# Nixie_Wrist_Clock_V1.net
KiCad netlist of a schematic drawn in EAGLE
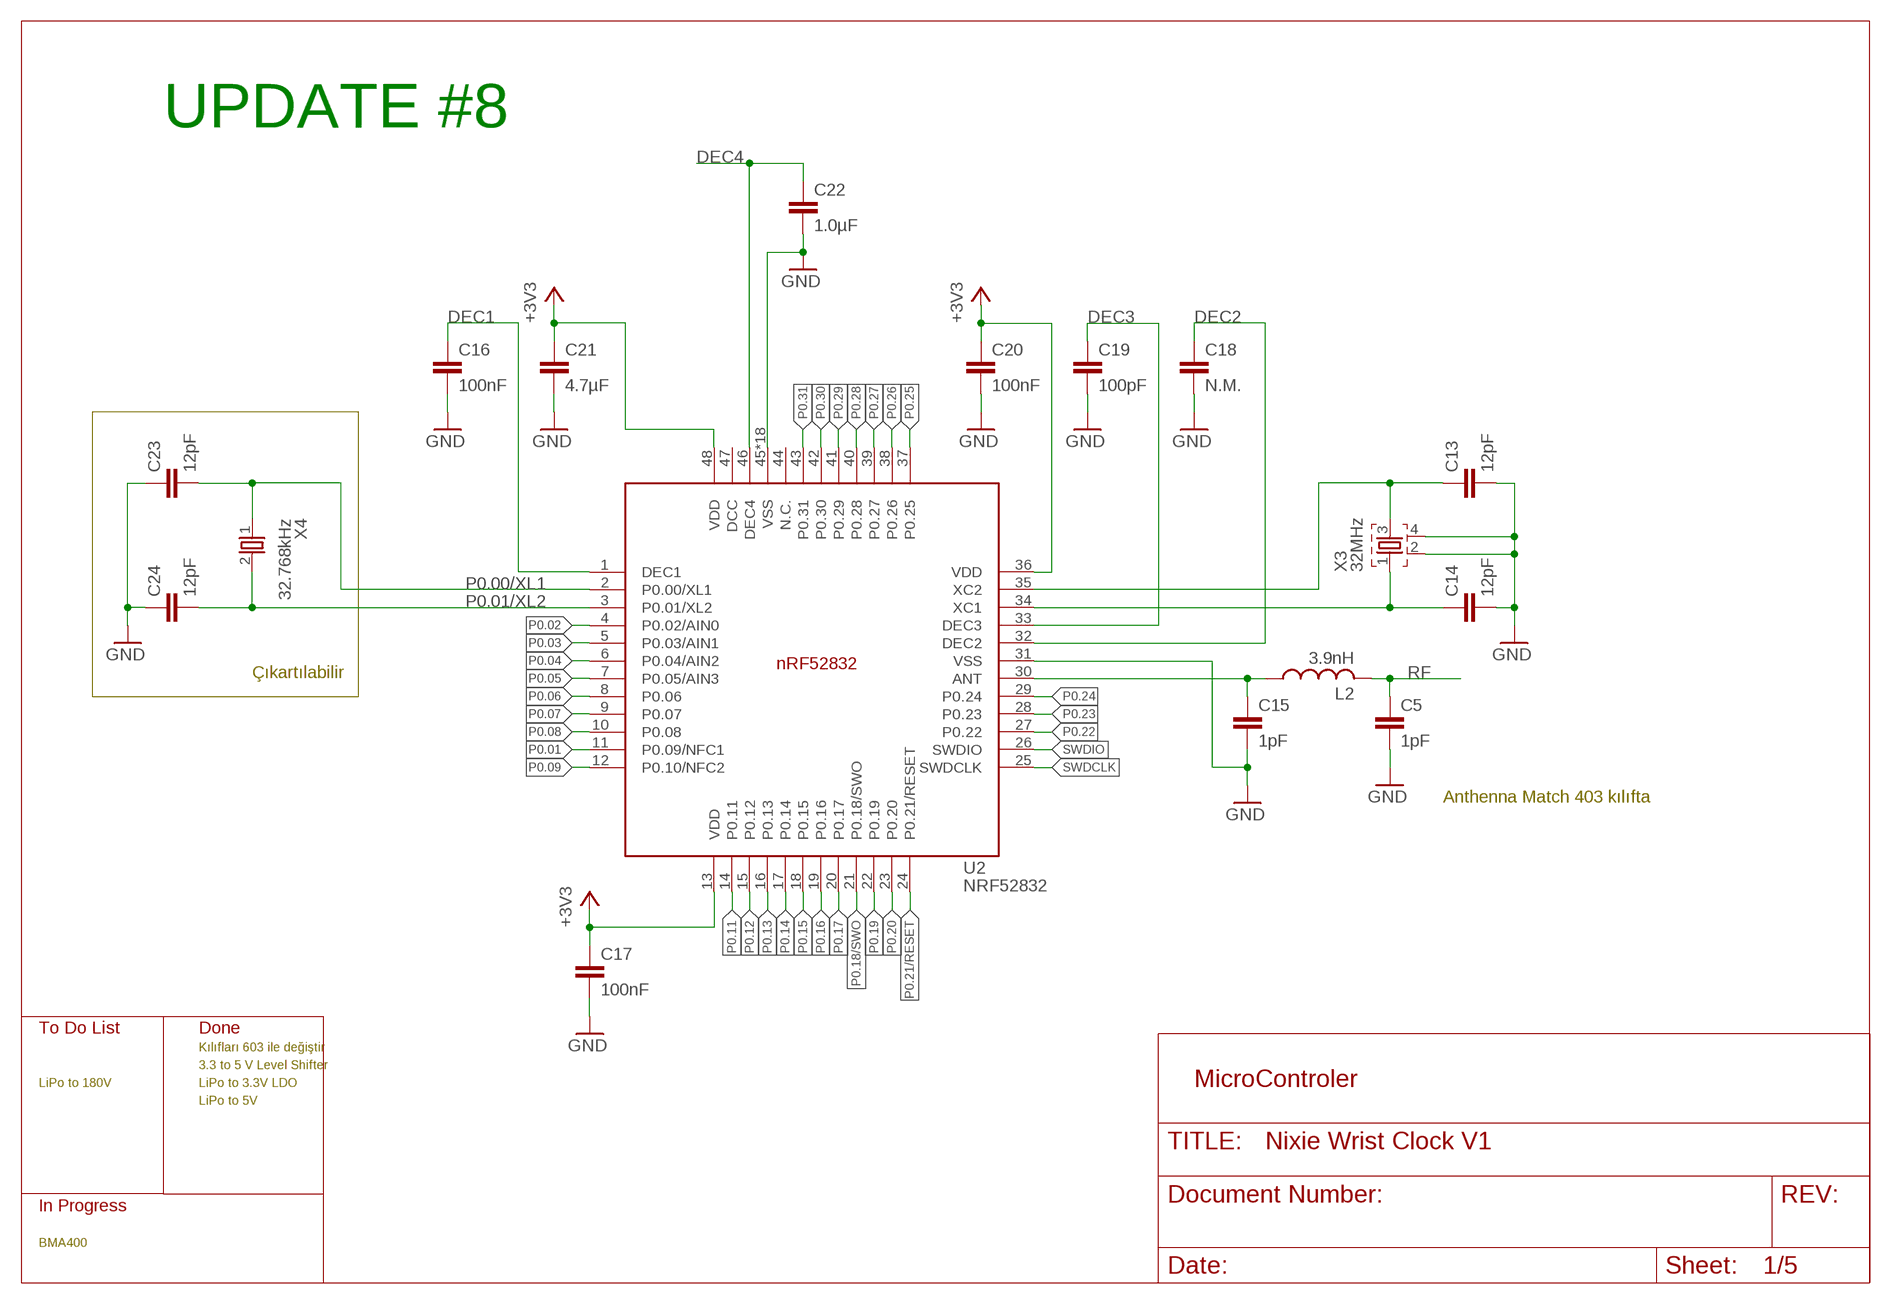
[diagram p0: schematic, sheet 1]
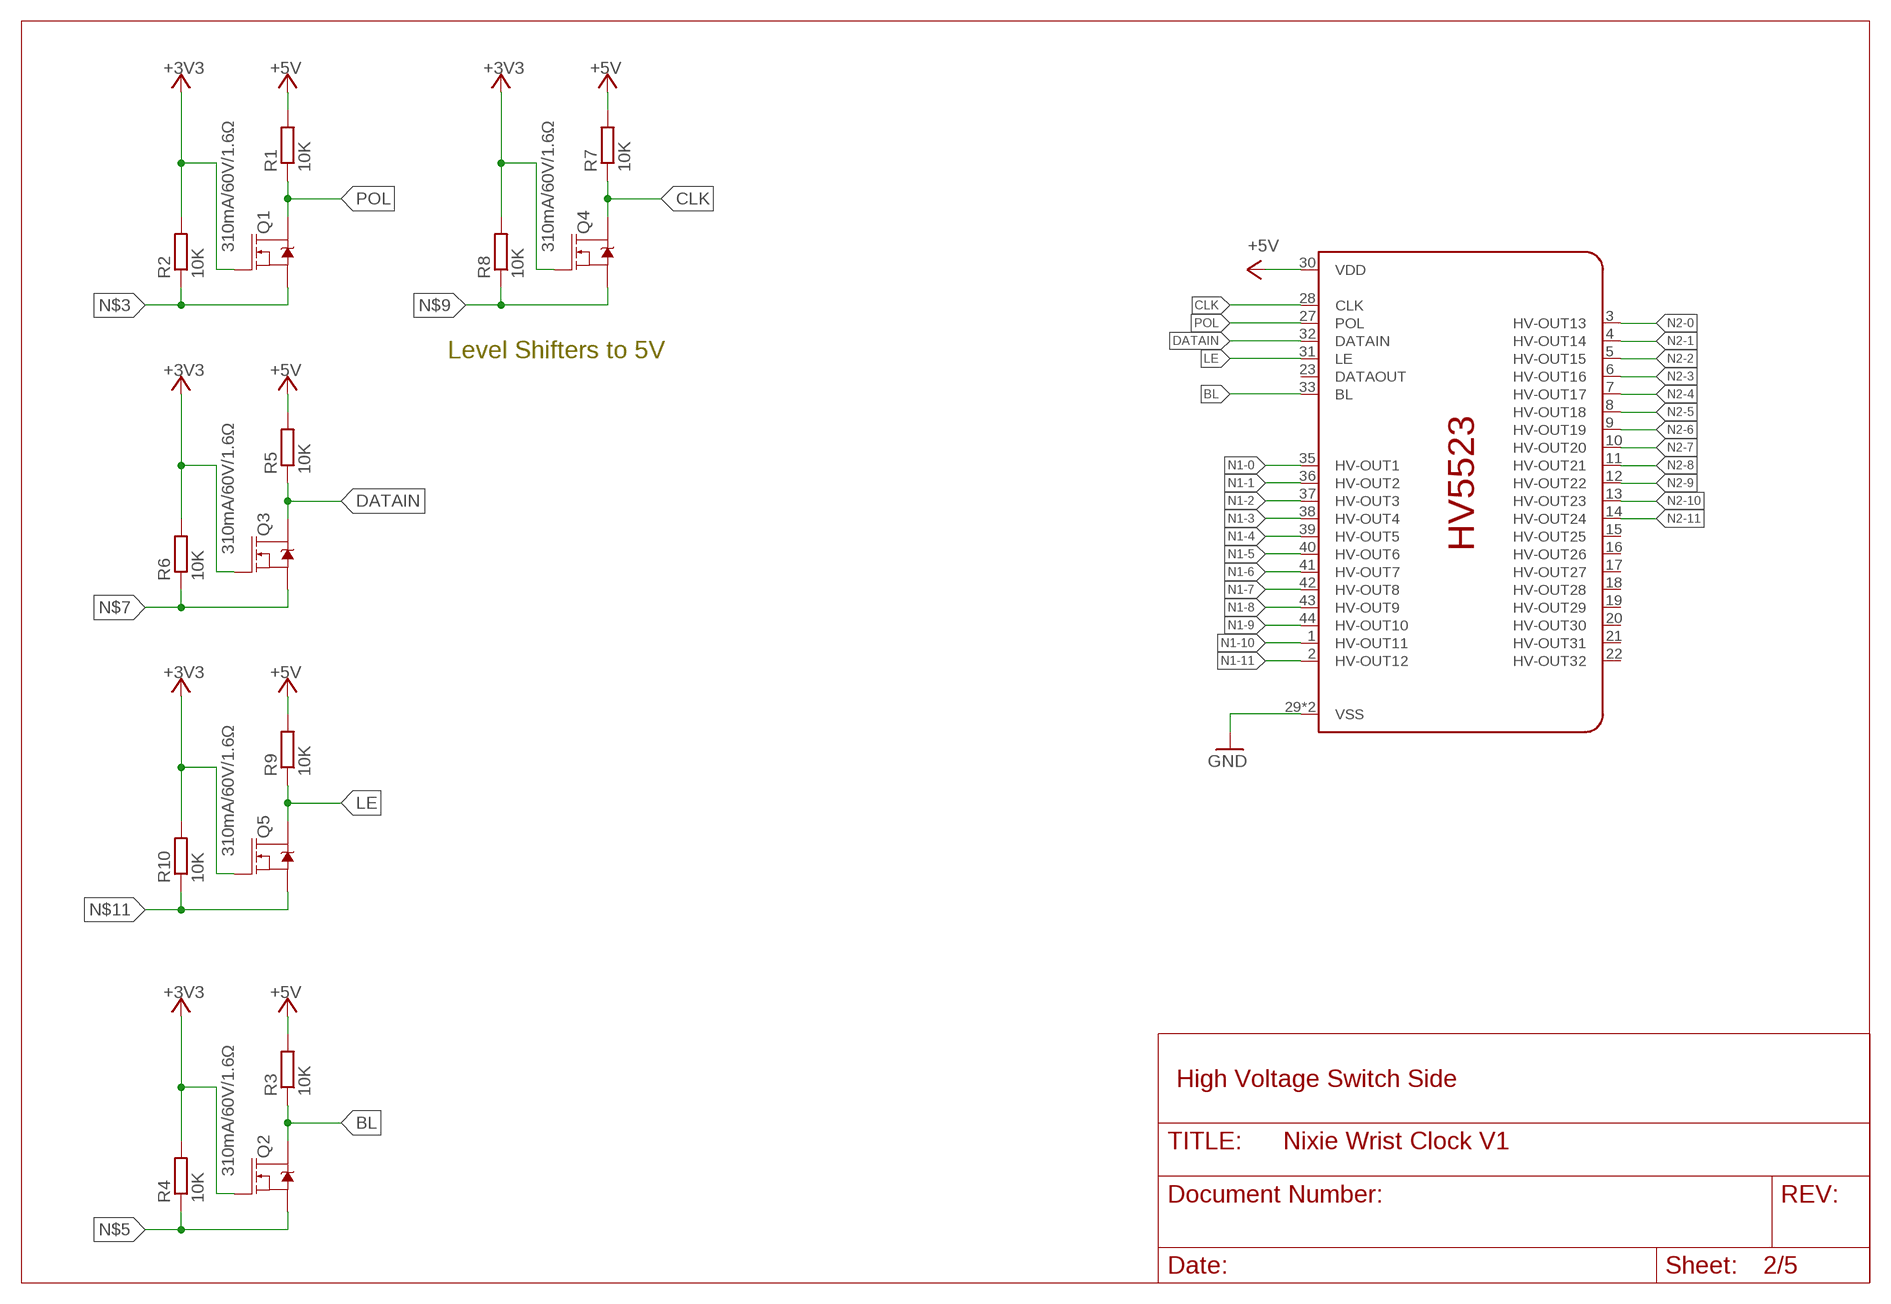
[diagram p1: schematic, sheet 2]
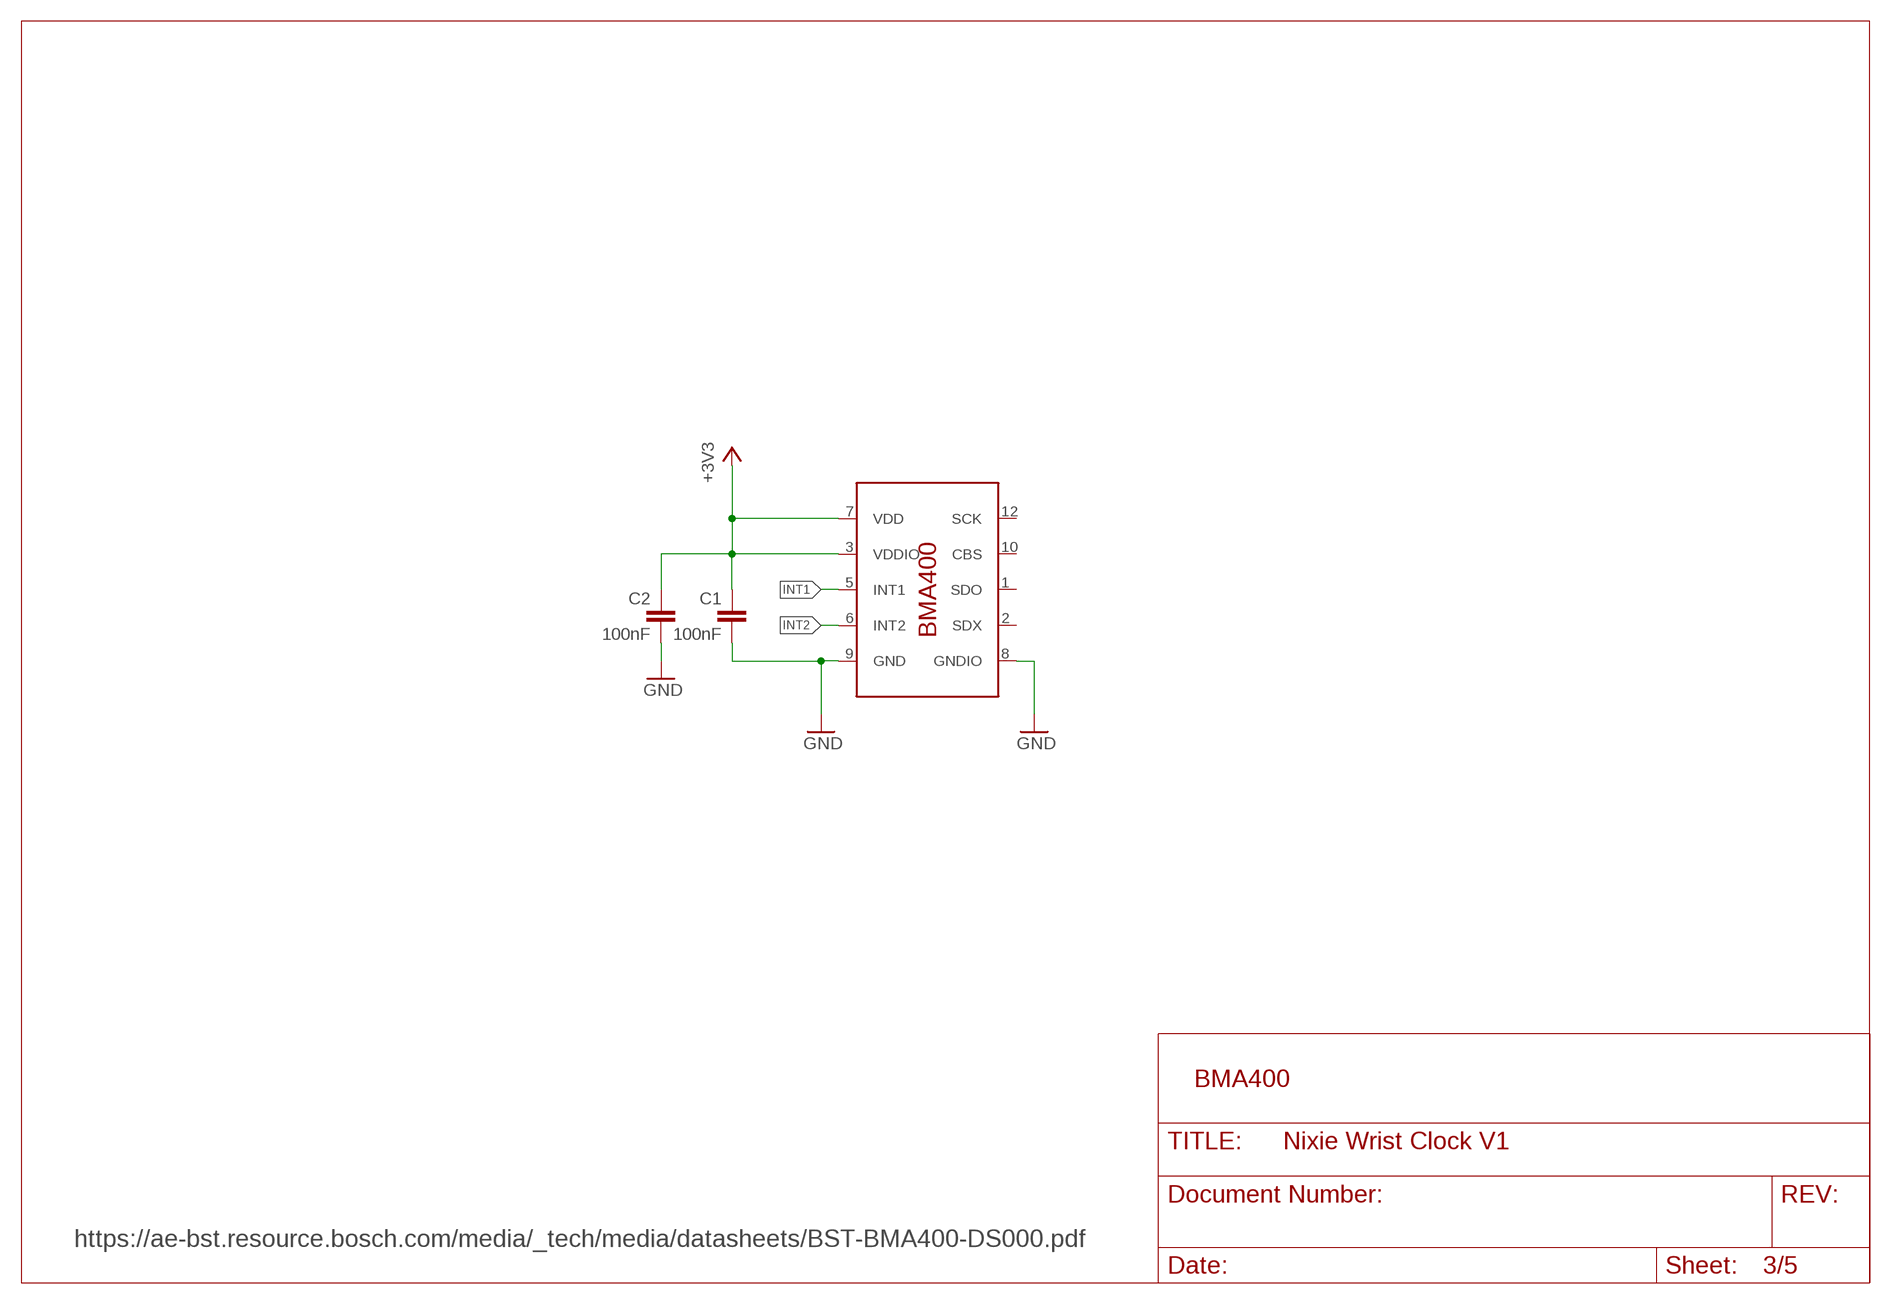
[diagram p2: schematic, sheet 3]
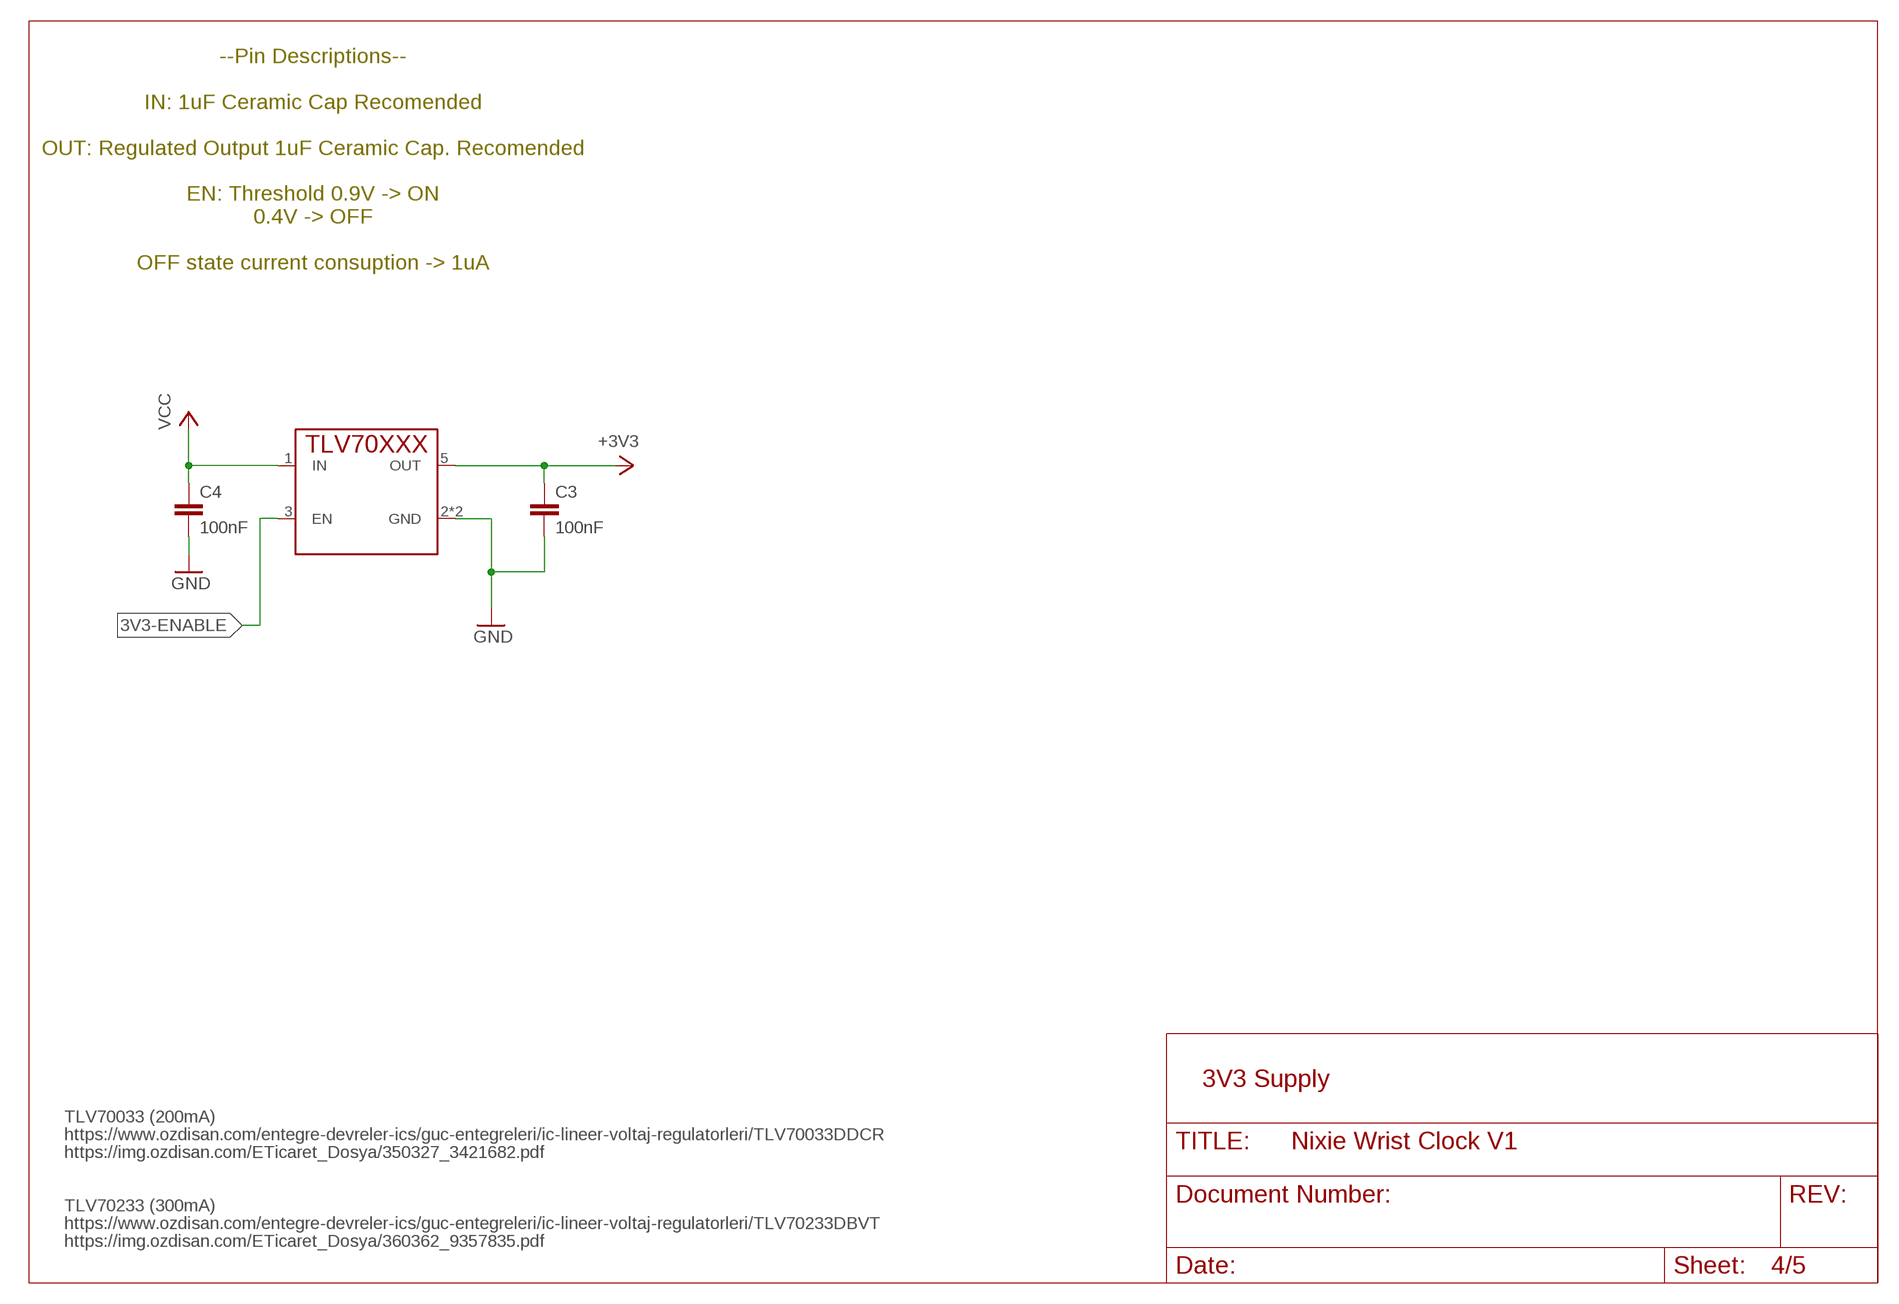
[diagram p3: schematic, sheet 4]
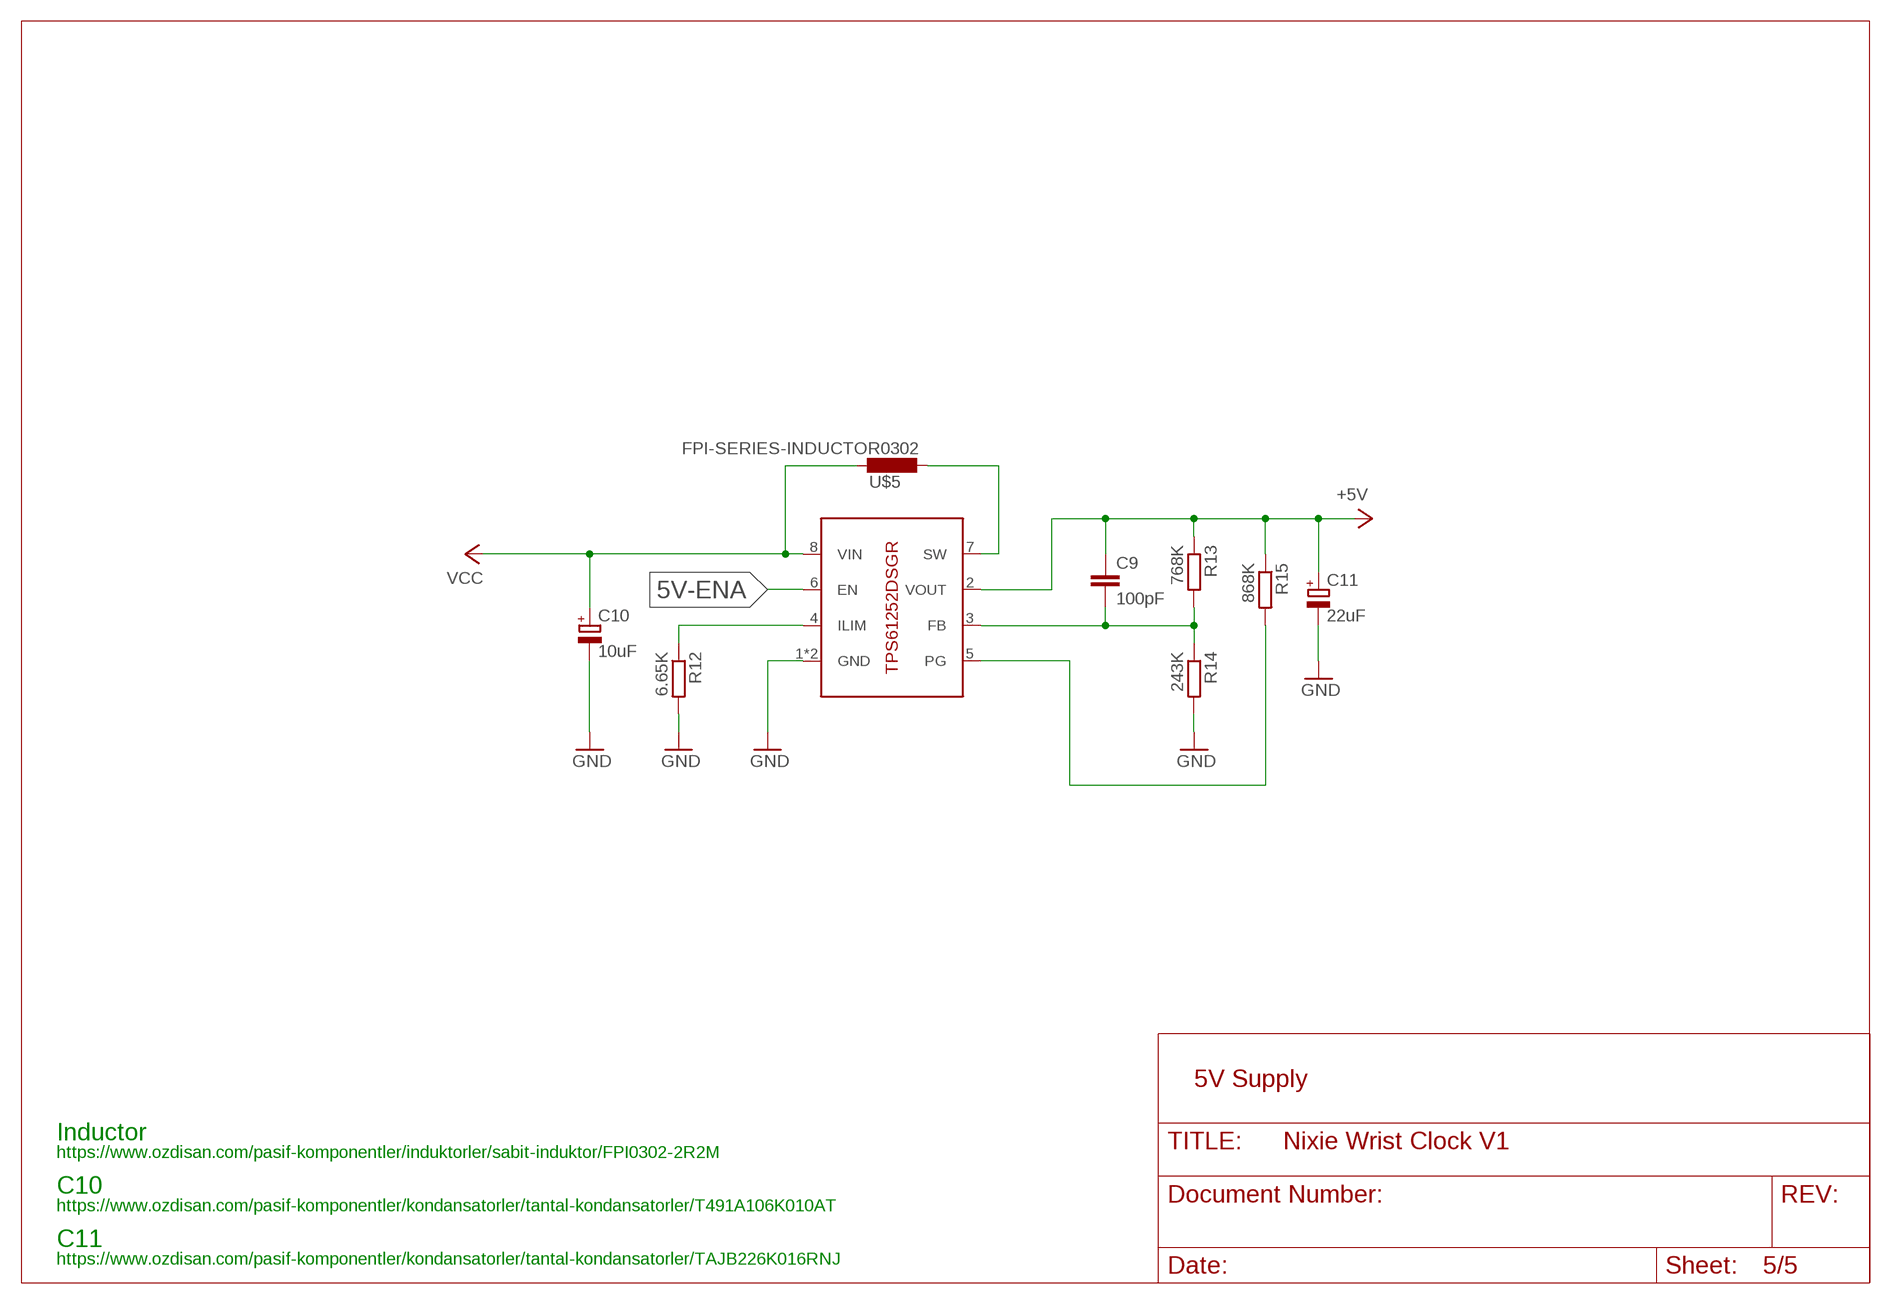
[diagram p4: schematic, sheet 5]

(export (version "E")
  (design (tool "Eeschema 10.0.6"))
  (components
    (comp (ref "C1")
      (value "100nF")
      (footprint "eagle-import:C0603K")
      (libsource (lib "eagle-import") (part "C-EUC0603K"))
    )
    (comp (ref "C2")
      (value "100nF")
      (footprint "eagle-import:C0603K")
      (libsource (lib "eagle-import") (part "C-EUC0603K"))
    )
    (comp (ref "U$1")
      (value "BMA400")
      (footprint "eagle-import:LGA-12")
      (libsource (lib "eagle-import") (part "BMA400"))
    )
    (comp (ref "C3")
      (value "100nF")
      (footprint "eagle-import:RESC0603_N")
      (libsource (lib "eagle-import") (part "CAPACITOR_0603_N"))
    )
    (comp (ref "C4")
      (value "100nF")
      (footprint "eagle-import:RESC0603_N")
      (libsource (lib "eagle-import") (part "CAPACITOR_0603_N"))
    )
    (comp (ref "U$3")
      (value "TLV70233SOT23-5")
      (footprint "eagle-import:SOT23-5")
      (libsource (lib "eagle-import") (part "TLV70233SOT23-5"))
    )
    (comp (ref "C5")
      (value "1pF")
      (footprint "eagle-import:RESC0402_N")
      (libsource (lib "eagle-import") (part "CAPACITOR_0402_N"))
    )
    (comp (ref "C13")
      (value "12pF")
      (footprint "eagle-import:RESC0603_N")
      (libsource (lib "eagle-import") (part "CAPACITOR_0603_N"))
    )
    (comp (ref "C14")
      (value "12pF")
      (footprint "eagle-import:RESC0603_N")
      (libsource (lib "eagle-import") (part "CAPACITOR_0603_N"))
    )
    (comp (ref "C15")
      (value "1pF")
      (footprint "eagle-import:RESC0402_N")
      (libsource (lib "eagle-import") (part "CAPACITOR_0402_N"))
    )
    (comp (ref "C16")
      (value "100nF")
      (footprint "eagle-import:RESC0603_N")
      (libsource (lib "eagle-import") (part "CAPACITOR_0603_N"))
    )
    (comp (ref "C17")
      (value "100nF")
      (footprint "eagle-import:RESC0603_N")
      (libsource (lib "eagle-import") (part "CAPACITOR_0603_N"))
    )
    (comp (ref "C18")
      (value "N.M.")
      (footprint "eagle-import:RESC0603_N")
      (libsource (lib "eagle-import") (part "CAPACITOR_0603_N"))
    )
    (comp (ref "C19")
      (value "100pF")
      (footprint "eagle-import:RESC0603_N")
      (libsource (lib "eagle-import") (part "CAPACITOR_0603_N"))
    )
    (comp (ref "C20")
      (value "100nF")
      (footprint "eagle-import:RESC0603_N")
      (libsource (lib "eagle-import") (part "CAPACITOR_0603_N"))
    )
    (comp (ref "C21")
      (value "4.7µF")
      (footprint "eagle-import:RESC0603_N")
      (libsource (lib "eagle-import") (part "CAPACITOR_0603_N"))
    )
    (comp (ref "C22")
      (value "1.0µF")
      (footprint "eagle-import:RESC0603_N")
      (libsource (lib "eagle-import") (part "CAPACITOR_0603_N"))
    )
    (comp (ref "C23")
      (value "12pF")
      (footprint "eagle-import:RESC0603_N")
      (libsource (lib "eagle-import") (part "CAPACITOR_0603_N"))
    )
    (comp (ref "C24")
      (value "12pF")
      (footprint "eagle-import:RESC0603_N")
      (libsource (lib "eagle-import") (part "CAPACITOR_0603_N"))
    )
    (comp (ref "L2")
      (value "3.9nH")
      (footprint "eagle-import:RESC0402_N")
      (libsource (lib "eagle-import") (part "INDUCTOR_0402_N"))
    )
    (comp (ref "U2")
      (value "NRF52832")
      (footprint "eagle-import:QFN40P600X600X90-48_N")
      (libsource (lib "eagle-import") (part "NRF52832"))
    )
    (comp (ref "X3")
      (value "32MHz")
      (footprint "eagle-import:BT-XTAL_2016_N")
      (libsource (lib "eagle-import") (part "XTAL_32MHZ"))
    )
    (comp (ref "X4")
      (value "32.768kHz")
      (footprint "eagle-import:XTAL_3215_N")
      (libsource (lib "eagle-import") (part "XTAL_32KHZ"))
    )
    (comp (ref "C9")
      (value "100pF")
      (footprint "eagle-import:RESC0603_N")
      (libsource (lib "eagle-import") (part "CAPACITOR_0603_N"))
    )
    (comp (ref "C10")
      (value "10uF")
      (footprint "eagle-import:SMC_A")
      (libsource (lib "eagle-import") (part "CPOL-EUSMCA"))
    )
    (comp (ref "C11")
      (value "22uF")
      (footprint "eagle-import:SMC_B")
      (libsource (lib "eagle-import") (part "CPOL-EUSMCB"))
    )
    (comp (ref "R12")
      (value "6.65K")
      (footprint "eagle-import:R0603")
      (libsource (lib "eagle-import") (part "R-EU_R0603"))
    )
    (comp (ref "R13")
      (value "768K")
      (footprint "eagle-import:R0603")
      (libsource (lib "eagle-import") (part "R-EU_R0603"))
    )
    (comp (ref "R14")
      (value "243K")
      (footprint "eagle-import:R0603")
      (libsource (lib "eagle-import") (part "R-EU_R0603"))
    )
    (comp (ref "R15")
      (value "868K")
      (footprint "eagle-import:R0603")
      (libsource (lib "eagle-import") (part "R-EU_R0603"))
    )
    (comp (ref "U$4")
      (value "TPS61252DSGR")
      (footprint "eagle-import:WSON-8-PAD")
      (libsource (lib "eagle-import") (part "TPS61252DSGR"))
    )
    (comp (ref "U$5")
      (value "FPI-SERIES-INDUCTOR0302")
      (footprint "eagle-import:FPI-0302")
      (libsource (lib "eagle-import") (part "FPI-SERIES-INDUCTOR0302"))
    )
    (comp (ref "Q1")
      (value "310mA/60V/1.6Ω")
      (footprint "eagle-import:SOT323")
      (libsource (lib "eagle-import") (part "MOSFET-NCH-2N7002PW"))
    )
    (comp (ref "Q2")
      (value "310mA/60V/1.6Ω")
      (footprint "eagle-import:SOT323")
      (libsource (lib "eagle-import") (part "MOSFET-NCH-2N7002PW"))
    )
    (comp (ref "Q3")
      (value "310mA/60V/1.6Ω")
      (footprint "eagle-import:SOT323")
      (libsource (lib "eagle-import") (part "MOSFET-NCH-2N7002PW"))
    )
    (comp (ref "Q4")
      (value "310mA/60V/1.6Ω")
      (footprint "eagle-import:SOT323")
      (libsource (lib "eagle-import") (part "MOSFET-NCH-2N7002PW"))
    )
    (comp (ref "Q5")
      (value "310mA/60V/1.6Ω")
      (footprint "eagle-import:SOT323")
      (libsource (lib "eagle-import") (part "MOSFET-NCH-2N7002PW"))
    )
    (comp (ref "R1")
      (value "10K")
      (footprint "eagle-import:R0603")
      (libsource (lib "eagle-import") (part "R-EU_R0603"))
    )
    (comp (ref "R2")
      (value "10K")
      (footprint "eagle-import:R0603")
      (libsource (lib "eagle-import") (part "R-EU_R0603"))
    )
    (comp (ref "R3")
      (value "10K")
      (footprint "eagle-import:R0603")
      (libsource (lib "eagle-import") (part "R-EU_R0603"))
    )
    (comp (ref "R4")
      (value "10K")
      (footprint "eagle-import:R0603")
      (libsource (lib "eagle-import") (part "R-EU_R0603"))
    )
    (comp (ref "R5")
      (value "10K")
      (footprint "eagle-import:R0603")
      (libsource (lib "eagle-import") (part "R-EU_R0603"))
    )
    (comp (ref "R6")
      (value "10K")
      (footprint "eagle-import:R0603")
      (libsource (lib "eagle-import") (part "R-EU_R0603"))
    )
    (comp (ref "R7")
      (value "10K")
      (footprint "eagle-import:R0603")
      (libsource (lib "eagle-import") (part "R-EU_R0603"))
    )
    (comp (ref "R8")
      (value "10K")
      (footprint "eagle-import:R0603")
      (libsource (lib "eagle-import") (part "R-EU_R0603"))
    )
    (comp (ref "R9")
      (value "10K")
      (footprint "eagle-import:R0603")
      (libsource (lib "eagle-import") (part "R-EU_R0603"))
    )
    (comp (ref "R10")
      (value "10K")
      (footprint "eagle-import:R0603")
      (libsource (lib "eagle-import") (part "R-EU_R0603"))
    )
    (comp (ref "U$2")
      (value "HV5523K7")
      (footprint "eagle-import:QFN50P707X707X80-45T515")
      (libsource (lib "eagle-import") (part "HV5523K7"))
    )
  )
  (nets
    (net (code "1") (name "+3V3") (class "Default")
      (node (ref "C1") (pin "2") (pinfunction "2_2") (pintype "passive"))
      (node (ref "C17") (pin "1") (pinfunction "1_1") (pintype "passive"))
      (node (ref "C2") (pin "1") (pinfunction "1_1") (pintype "passive"))
      (node (ref "C20") (pin "1") (pinfunction "1_1") (pintype "passive"))
      (node (ref "C21") (pin "1") (pinfunction "1_1") (pintype "passive"))
      (node (ref "C3") (pin "1") (pinfunction "1_1") (pintype "passive"))
      (node (ref "Q1") (pin "1") (pinfunction "G_1") (pintype "bidirectional"))
      (node (ref "Q2") (pin "1") (pinfunction "G_1") (pintype "bidirectional"))
      (node (ref "Q3") (pin "1") (pinfunction "G_1") (pintype "bidirectional"))
      (node (ref "Q4") (pin "1") (pinfunction "G_1") (pintype "bidirectional"))
      (node (ref "Q5") (pin "1") (pinfunction "G_1") (pintype "bidirectional"))
      (node (ref "R10") (pin "2") (pinfunction "2_2") (pintype "passive"))
      (node (ref "R2") (pin "2") (pinfunction "2_2") (pintype "passive"))
      (node (ref "R4") (pin "2") (pinfunction "2_2") (pintype "passive"))
      (node (ref "R6") (pin "2") (pinfunction "2_2") (pintype "passive"))
      (node (ref "R8") (pin "2") (pinfunction "2_2") (pintype "passive"))
      (node (ref "U$1") (pin "3") (pinfunction "VDDIO_3") (pintype "bidirectional"))
      (node (ref "U$1") (pin "7") (pinfunction "VDD_7") (pintype "bidirectional"))
      (node (ref "U$3") (pin "5") (pinfunction "OUT_5") (pintype "output"))
      (node (ref "U2") (pin "13") (pinfunction "VDD_13") (pintype "power_in"))
      (node (ref "U2") (pin "36") (pinfunction "VDD_36") (pintype "power_in"))
      (node (ref "U2") (pin "48") (pinfunction "VDD_48") (pintype "power_in"))
    )
    (net (code "2") (name "+5V") (class "Default")
      (node (ref "C11") (pin "+") (pinfunction "+_+") (pintype "passive"))
      (node (ref "C9") (pin "1") (pinfunction "1_1") (pintype "passive"))
      (node (ref "R1") (pin "2") (pinfunction "2_2") (pintype "passive"))
      (node (ref "R13") (pin "1") (pinfunction "1_1") (pintype "passive"))
      (node (ref "R15") (pin "1") (pinfunction "1_1") (pintype "passive"))
      (node (ref "R3") (pin "2") (pinfunction "2_2") (pintype "passive"))
      (node (ref "R5") (pin "2") (pinfunction "2_2") (pintype "passive"))
      (node (ref "R7") (pin "2") (pinfunction "2_2") (pintype "passive"))
      (node (ref "R9") (pin "2") (pinfunction "2_2") (pintype "passive"))
      (node (ref "U$2") (pin "30") (pinfunction "VDD_30") (pintype "bidirectional"))
      (node (ref "U$4") (pin "2") (pinfunction "VOUT_2") (pintype "bidirectional"))
    )
    (net (code "3") (name "3V3-ENABLE") (class "Default")
      (node (ref "U$3") (pin "3") (pinfunction "EN_3") (pintype "input"))
    )
    (net (code "4") (name "5V-ENA") (class "Default")
      (node (ref "U$4") (pin "6") (pinfunction "EN_6") (pintype "bidirectional"))
    )
    (net (code "5") (name "BL") (class "Default")
      (node (ref "Q2") (pin "3") (pinfunction "D_3") (pintype "bidirectional"))
      (node (ref "R3") (pin "1") (pinfunction "1_1") (pintype "passive"))
      (node (ref "U$2") (pin "33") (pinfunction "BL_33") (pintype "bidirectional"))
    )
    (net (code "6") (name "CLK") (class "Default")
      (node (ref "Q4") (pin "3") (pinfunction "D_3") (pintype "bidirectional"))
      (node (ref "R7") (pin "1") (pinfunction "1_1") (pintype "passive"))
      (node (ref "U$2") (pin "28") (pinfunction "CLK_28") (pintype "bidirectional"))
    )
    (net (code "7") (name "DATAIN") (class "Default")
      (node (ref "Q3") (pin "3") (pinfunction "D_3") (pintype "bidirectional"))
      (node (ref "R5") (pin "1") (pinfunction "1_1") (pintype "passive"))
      (node (ref "U$2") (pin "32") (pinfunction "DATAIN_32") (pintype "bidirectional"))
    )
    (net (code "8") (name "DEC1") (class "Default")
      (node (ref "C16") (pin "1") (pinfunction "1_1") (pintype "passive"))
      (node (ref "U2") (pin "1") (pinfunction "DEC1_1") (pintype "power_in"))
    )
    (net (code "9") (name "DEC2") (class "Default")
      (node (ref "C18") (pin "1") (pinfunction "1_1") (pintype "passive"))
      (node (ref "U2") (pin "32") (pinfunction "DEC2_32") (pintype "bidirectional"))
    )
    (net (code "10") (name "DEC3") (class "Default")
      (node (ref "C19") (pin "1") (pinfunction "1_1") (pintype "passive"))
      (node (ref "U2") (pin "33") (pinfunction "DEC3_33") (pintype "bidirectional"))
    )
    (net (code "11") (name "DEC4") (class "Default")
      (node (ref "C22") (pin "1") (pinfunction "1_1") (pintype "passive"))
      (node (ref "U2") (pin "46") (pinfunction "DEC4_46") (pintype "power_in"))
    )
    (net (code "12") (name "GND") (class "Default")
      (node (ref "C1") (pin "1") (pinfunction "1_1") (pintype "passive"))
      (node (ref "C10") (pin "-") (pinfunction "-_-") (pintype "passive"))
      (node (ref "C11") (pin "-") (pinfunction "-_-") (pintype "passive"))
      (node (ref "C13") (pin "2") (pinfunction "2_2") (pintype "passive"))
      (node (ref "C14") (pin "2") (pinfunction "2_2") (pintype "passive"))
      (node (ref "C15") (pin "2") (pinfunction "2_2") (pintype "passive"))
      (node (ref "C16") (pin "2") (pinfunction "2_2") (pintype "passive"))
      (node (ref "C17") (pin "2") (pinfunction "2_2") (pintype "passive"))
      (node (ref "C18") (pin "2") (pinfunction "2_2") (pintype "passive"))
      (node (ref "C19") (pin "2") (pinfunction "2_2") (pintype "passive"))
      (node (ref "C2") (pin "2") (pinfunction "2_2") (pintype "passive"))
      (node (ref "C20") (pin "2") (pinfunction "2_2") (pintype "passive"))
      (node (ref "C21") (pin "2") (pinfunction "2_2") (pintype "passive"))
      (node (ref "C22") (pin "2") (pinfunction "2_2") (pintype "passive"))
      (node (ref "C23") (pin "1") (pinfunction "1_1") (pintype "passive"))
      (node (ref "C24") (pin "1") (pinfunction "1_1") (pintype "passive"))
      (node (ref "C3") (pin "2") (pinfunction "2_2") (pintype "passive"))
      (node (ref "C4") (pin "2") (pinfunction "2_2") (pintype "passive"))
      (node (ref "C5") (pin "2") (pinfunction "2_2") (pintype "passive"))
      (node (ref "R12") (pin "2") (pinfunction "2_2") (pintype "passive"))
      (node (ref "R14") (pin "2") (pinfunction "2_2") (pintype "passive"))
      (node (ref "U$1") (pin "8") (pinfunction "GNDIO_8") (pintype "bidirectional"))
      (node (ref "U$1") (pin "9") (pinfunction "GND_9") (pintype "bidirectional"))
      (node (ref "U$2") (pin "29") (pinfunction "VSS_29") (pintype "bidirectional"))
      (node (ref "U$2") (pin "45") (pinfunction "VSS_45") (pintype "bidirectional"))
      (node (ref "U$3") (pin "2") (pinfunction "GND_2") (pintype "bidirectional"))
      (node (ref "U$3") (pin "4") (pinfunction "GND_4") (pintype "bidirectional"))
      (node (ref "U$4") (pin "1") (pinfunction "GND_1") (pintype "bidirectional"))
      (node (ref "U$4") (pin "PAD") (pinfunction "GND_PAD") (pintype "bidirectional"))
      (node (ref "U2") (pin "31") (pinfunction "VSS_31") (pintype "bidirectional"))
      (node (ref "U2") (pin "45") (pinfunction "VSS_45") (pintype "power_in"))
      (node (ref "U2") (pin "PAD") (pinfunction "VSS_PAD") (pintype "power_in"))
      (node (ref "U2") (pin "PAD@VIA01") (pinfunction "VSS_PAD@VIA01") (pintype "power_in"))
      (node (ref "U2") (pin "PAD@VIA02") (pinfunction "VSS_PAD@VIA02") (pintype "power_in"))
      (node (ref "U2") (pin "PAD@VIA03") (pinfunction "VSS_PAD@VIA03") (pintype "power_in"))
      (node (ref "U2") (pin "PAD@VIA04") (pinfunction "VSS_PAD@VIA04") (pintype "power_in"))
      (node (ref "U2") (pin "PAD@VIA05") (pinfunction "VSS_PAD@VIA05") (pintype "power_in"))
      (node (ref "U2") (pin "PAD@VIA06") (pinfunction "VSS_PAD@VIA06") (pintype "power_in"))
      (node (ref "U2") (pin "PAD@VIA07") (pinfunction "VSS_PAD@VIA07") (pintype "power_in"))
      (node (ref "U2") (pin "PAD@VIA08") (pinfunction "VSS_PAD@VIA08") (pintype "power_in"))
      (node (ref "U2") (pin "PAD@VIA09") (pinfunction "VSS_PAD@VIA09") (pintype "power_in"))
      (node (ref "U2") (pin "PAD@VIA10") (pinfunction "VSS_PAD@VIA10") (pintype "power_in"))
      (node (ref "U2") (pin "PAD@VIA11") (pinfunction "VSS_PAD@VIA11") (pintype "power_in"))
      (node (ref "U2") (pin "PAD@VIA12") (pinfunction "VSS_PAD@VIA12") (pintype "power_in"))
      (node (ref "U2") (pin "PAD@VIA13") (pinfunction "VSS_PAD@VIA13") (pintype "power_in"))
      (node (ref "U2") (pin "PAD@VIA14") (pinfunction "VSS_PAD@VIA14") (pintype "power_in"))
      (node (ref "U2") (pin "PAD@VIA15") (pinfunction "VSS_PAD@VIA15") (pintype "power_in"))
      (node (ref "U2") (pin "PAD@VIA16") (pinfunction "VSS_PAD@VIA16") (pintype "power_in"))
      (node (ref "X3") (pin "2") (pinfunction "2_2") (pintype "passive"))
      (node (ref "X3") (pin "4") (pinfunction "4_4") (pintype "passive"))
    )
    (net (code "13") (name "INT1") (class "Default")
      (node (ref "U$1") (pin "5") (pinfunction "INT1_5") (pintype "bidirectional"))
    )
    (net (code "14") (name "INT2") (class "Default")
      (node (ref "U$1") (pin "6") (pinfunction "INT2_6") (pintype "bidirectional"))
    )
    (net (code "15") (name "LE") (class "Default")
      (node (ref "Q5") (pin "3") (pinfunction "D_3") (pintype "bidirectional"))
      (node (ref "R9") (pin "1") (pinfunction "1_1") (pintype "passive"))
      (node (ref "U$2") (pin "31") (pinfunction "LE_31") (pintype "bidirectional"))
    )
    (net (code "16") (name "N$3") (class "Default")
      (node (ref "Q1") (pin "2") (pinfunction "S_2") (pintype "bidirectional"))
      (node (ref "R2") (pin "1") (pinfunction "1_1") (pintype "passive"))
    )
    (net (code "17") (name "N$5") (class "Default")
      (node (ref "Q2") (pin "2") (pinfunction "S_2") (pintype "bidirectional"))
      (node (ref "R4") (pin "1") (pinfunction "1_1") (pintype "passive"))
    )
    (net (code "18") (name "N$7") (class "Default")
      (node (ref "Q3") (pin "2") (pinfunction "S_2") (pintype "bidirectional"))
      (node (ref "R6") (pin "1") (pinfunction "1_1") (pintype "passive"))
    )
    (net (code "19") (name "N$9") (class "Default")
      (node (ref "Q4") (pin "2") (pinfunction "S_2") (pintype "bidirectional"))
      (node (ref "R8") (pin "1") (pinfunction "1_1") (pintype "passive"))
    )
    (net (code "20") (name "N$11") (class "Default")
      (node (ref "Q5") (pin "2") (pinfunction "S_2") (pintype "bidirectional"))
      (node (ref "R10") (pin "1") (pinfunction "1_1") (pintype "passive"))
    )
    (net (code "21") (name "N1-0") (class "Default")
      (node (ref "U$2") (pin "35") (pinfunction "HV-OUT1_35") (pintype "bidirectional"))
    )
    (net (code "22") (name "N1-1") (class "Default")
      (node (ref "U$2") (pin "36") (pinfunction "HV-OUT2_36") (pintype "bidirectional"))
    )
    (net (code "23") (name "N1-2") (class "Default")
      (node (ref "U$2") (pin "37") (pinfunction "HV-OUT3_37") (pintype "bidirectional"))
    )
    (net (code "24") (name "N1-3") (class "Default")
      (node (ref "U$2") (pin "38") (pinfunction "HV-OUT4_38") (pintype "bidirectional"))
    )
    (net (code "25") (name "N1-4") (class "Default")
      (node (ref "U$2") (pin "39") (pinfunction "HV-OUT5_39") (pintype "bidirectional"))
    )
    (net (code "26") (name "N1-5") (class "Default")
      (node (ref "U$2") (pin "40") (pinfunction "HV-OUT6_40") (pintype "bidirectional"))
    )
    (net (code "27") (name "N1-6") (class "Default")
      (node (ref "U$2") (pin "41") (pinfunction "HV-OUT7_41") (pintype "bidirectional"))
    )
    (net (code "28") (name "N1-7") (class "Default")
      (node (ref "U$2") (pin "42") (pinfunction "HV-OUT8_42") (pintype "bidirectional"))
    )
    (net (code "29") (name "N1-8") (class "Default")
      (node (ref "U$2") (pin "43") (pinfunction "HV-OUT9_43") (pintype "bidirectional"))
    )
    (net (code "30") (name "N1-9") (class "Default")
      (node (ref "U$2") (pin "44") (pinfunction "HV-OUT10_44") (pintype "bidirectional"))
    )
    (net (code "31") (name "N1-10") (class "Default")
      (node (ref "U$2") (pin "1") (pinfunction "HV-OUT11_1") (pintype "bidirectional"))
    )
    (net (code "32") (name "N1-11") (class "Default")
      (node (ref "U$2") (pin "2") (pinfunction "HV-OUT12_2") (pintype "bidirectional"))
    )
    (net (code "33") (name "N2-0") (class "Default")
      (node (ref "U$2") (pin "3") (pinfunction "HV-OUT13_3") (pintype "bidirectional"))
    )
    (net (code "34") (name "N2-1") (class "Default")
      (node (ref "U$2") (pin "4") (pinfunction "HV-OUT14_4") (pintype "bidirectional"))
    )
    (net (code "35") (name "N2-2") (class "Default")
      (node (ref "U$2") (pin "5") (pinfunction "HV-OUT15_5") (pintype "bidirectional"))
    )
    (net (code "36") (name "N2-3") (class "Default")
      (node (ref "U$2") (pin "6") (pinfunction "HV-OUT16_6") (pintype "bidirectional"))
    )
    (net (code "37") (name "N2-4") (class "Default")
      (node (ref "U$2") (pin "7") (pinfunction "HV-OUT17_7") (pintype "bidirectional"))
    )
    (net (code "38") (name "N2-5") (class "Default")
      (node (ref "U$2") (pin "8") (pinfunction "HV-OUT18_8") (pintype "bidirectional"))
    )
    (net (code "39") (name "N2-6") (class "Default")
      (node (ref "U$2") (pin "9") (pinfunction "HV-OUT19_9") (pintype "bidirectional"))
    )
    (net (code "40") (name "N2-7") (class "Default")
      (node (ref "U$2") (pin "10") (pinfunction "HV-OUT20_10") (pintype "bidirectional"))
    )
    (net (code "41") (name "N2-8") (class "Default")
      (node (ref "U$2") (pin "11") (pinfunction "HV-OUT21_11") (pintype "bidirectional"))
    )
    (net (code "42") (name "N2-9") (class "Default")
      (node (ref "U$2") (pin "12") (pinfunction "HV-OUT22_12") (pintype "bidirectional"))
    )
    (net (code "43") (name "N2-10") (class "Default")
      (node (ref "U$2") (pin "13") (pinfunction "HV-OUT23_13") (pintype "bidirectional"))
    )
    (net (code "44") (name "N2-11") (class "Default")
      (node (ref "U$2") (pin "14") (pinfunction "HV-OUT24_14") (pintype "bidirectional"))
    )
    (net (code "45") (name "Net-(U$4-FB)") (class "Default")
      (node (ref "C9") (pin "2") (pinfunction "2_2") (pintype "passive"))
      (node (ref "R13") (pin "2") (pinfunction "2_2") (pintype "passive"))
      (node (ref "R14") (pin "1") (pinfunction "1_1") (pintype "passive"))
      (node (ref "U$4") (pin "3") (pinfunction "FB_3") (pintype "bidirectional"))
    )
    (net (code "46") (name "Net-(U$4-ILIM)") (class "Default")
      (node (ref "R12") (pin "1") (pinfunction "1_1") (pintype "passive"))
      (node (ref "U$4") (pin "4") (pinfunction "ILIM_4") (pintype "bidirectional"))
    )
    (net (code "47") (name "Net-(U$4-PG)") (class "Default")
      (node (ref "R15") (pin "2") (pinfunction "2_2") (pintype "passive"))
      (node (ref "U$4") (pin "5") (pinfunction "PG_5") (pintype "bidirectional"))
    )
    (net (code "48") (name "Net-(U$4-SW)") (class "Default")
      (node (ref "U$4") (pin "7") (pinfunction "SW_7") (pintype "bidirectional"))
      (node (ref "U$5") (pin "P$2") (pinfunction "2_P$2") (pintype "passive"))
    )
    (net (code "49") (name "Net-(U2-ANT)") (class "Default")
      (node (ref "C15") (pin "1") (pinfunction "1_1") (pintype "passive"))
      (node (ref "L2") (pin "1") (pinfunction "1_1") (pintype "passive"))
      (node (ref "U2") (pin "30") (pinfunction "ANT_30") (pintype "bidirectional"))
    )
    (net (code "50") (name "Net-(U2-XC1)") (class "Default")
      (node (ref "C14") (pin "1") (pinfunction "1_1") (pintype "passive"))
      (node (ref "U2") (pin "34") (pinfunction "XC1_34") (pintype "input"))
      (node (ref "X3") (pin "1") (pinfunction "1_1") (pintype "passive"))
    )
    (net (code "51") (name "Net-(U2-XC2)") (class "Default")
      (node (ref "C13") (pin "1") (pinfunction "1_1") (pintype "passive"))
      (node (ref "U2") (pin "35") (pinfunction "XC2_35") (pintype "output"))
      (node (ref "X3") (pin "3") (pinfunction "3_3") (pintype "passive"))
    )
    (net (code "52") (name "P0.00{slash}XL1") (class "Default")
      (node (ref "C23") (pin "2") (pinfunction "2_2") (pintype "passive"))
      (node (ref "U2") (pin "2") (pinfunction "P0.00/XL1_2") (pintype "bidirectional"))
      (node (ref "X4") (pin "1") (pinfunction "1_1") (pintype "passive"))
    )
    (net (code "53") (name "P0.01") (class "Default")
      (node (ref "U2") (pin "11") (pinfunction "P0.09/NFC1_11") (pintype "bidirectional"))
    )
    (net (code "54") (name "P0.01{slash}XL2") (class "Default")
      (node (ref "C24") (pin "2") (pinfunction "2_2") (pintype "passive"))
      (node (ref "U2") (pin "3") (pinfunction "P0.01/XL2_3") (pintype "bidirectional"))
      (node (ref "X4") (pin "2") (pinfunction "2_2") (pintype "passive"))
    )
    (net (code "55") (name "P0.02") (class "Default")
      (node (ref "U2") (pin "4") (pinfunction "P0.02/AIN0_4") (pintype "bidirectional"))
    )
    (net (code "56") (name "P0.03") (class "Default")
      (node (ref "U2") (pin "5") (pinfunction "P0.03/AIN1_5") (pintype "bidirectional"))
    )
    (net (code "57") (name "P0.04") (class "Default")
      (node (ref "U2") (pin "6") (pinfunction "P0.04/AIN2_6") (pintype "bidirectional"))
    )
    (net (code "58") (name "P0.05") (class "Default")
      (node (ref "U2") (pin "7") (pinfunction "P0.05/AIN3_7") (pintype "bidirectional"))
    )
    (net (code "59") (name "P0.06") (class "Default")
      (node (ref "U2") (pin "8") (pinfunction "P0.06_8") (pintype "bidirectional"))
    )
    (net (code "60") (name "P0.07") (class "Default")
      (node (ref "U2") (pin "9") (pinfunction "P0.07_9") (pintype "bidirectional"))
    )
    (net (code "61") (name "P0.08") (class "Default")
      (node (ref "U2") (pin "10") (pinfunction "P0.08_10") (pintype "bidirectional"))
    )
    (net (code "62") (name "P0.09") (class "Default")
      (node (ref "U2") (pin "12") (pinfunction "P0.10/NFC2_12") (pintype "bidirectional"))
    )
    (net (code "63") (name "P0.11") (class "Default")
      (node (ref "U2") (pin "14") (pinfunction "P0.11_14") (pintype "bidirectional"))
    )
    (net (code "64") (name "P0.12") (class "Default")
      (node (ref "U2") (pin "15") (pinfunction "P0.12_15") (pintype "bidirectional"))
    )
    (net (code "65") (name "P0.13") (class "Default")
      (node (ref "U2") (pin "16") (pinfunction "P0.13_16") (pintype "bidirectional"))
    )
    (net (code "66") (name "P0.14") (class "Default")
      (node (ref "U2") (pin "17") (pinfunction "P0.14_17") (pintype "bidirectional"))
    )
    (net (code "67") (name "P0.15") (class "Default")
      (node (ref "U2") (pin "18") (pinfunction "P0.15_18") (pintype "bidirectional"))
    )
    (net (code "68") (name "P0.16") (class "Default")
      (node (ref "U2") (pin "19") (pinfunction "P0.16_19") (pintype "bidirectional"))
    )
    (net (code "69") (name "P0.17") (class "Default")
      (node (ref "U2") (pin "20") (pinfunction "P0.17_20") (pintype "bidirectional"))
    )
    (net (code "70") (name "P0.18{slash}SWO") (class "Default")
      (node (ref "U2") (pin "21") (pinfunction "P0.18/SWO_21") (pintype "bidirectional"))
    )
    (net (code "71") (name "P0.19") (class "Default")
      (node (ref "U2") (pin "22") (pinfunction "P0.19_22") (pintype "bidirectional"))
    )
    (net (code "72") (name "P0.20") (class "Default")
      (node (ref "U2") (pin "23") (pinfunction "P0.20_23") (pintype "bidirectional"))
    )
    (net (code "73") (name "P0.21{slash}RESET") (class "Default")
      (node (ref "U2") (pin "24") (pinfunction "P0.21/RESET_24") (pintype "bidirectional"))
    )
    (net (code "74") (name "P0.22") (class "Default")
      (node (ref "U2") (pin "27") (pinfunction "P0.22_27") (pintype "bidirectional"))
    )
    (net (code "75") (name "P0.23") (class "Default")
      (node (ref "U2") (pin "28") (pinfunction "P0.23_28") (pintype "bidirectional"))
    )
    (net (code "76") (name "P0.24") (class "Default")
      (node (ref "U2") (pin "29") (pinfunction "P0.24_29") (pintype "bidirectional"))
    )
    (net (code "77") (name "P0.25") (class "Default")
      (node (ref "U2") (pin "37") (pinfunction "P0.25_37") (pintype "bidirectional"))
    )
    (net (code "78") (name "P0.26") (class "Default")
      (node (ref "U2") (pin "38") (pinfunction "P0.26_38") (pintype "bidirectional"))
    )
    (net (code "79") (name "P0.27") (class "Default")
      (node (ref "U2") (pin "39") (pinfunction "P0.27_39") (pintype "bidirectional"))
    )
    (net (code "80") (name "P0.28") (class "Default")
      (node (ref "U2") (pin "40") (pinfunction "P0.28_40") (pintype "bidirectional"))
    )
    (net (code "81") (name "P0.29") (class "Default")
      (node (ref "U2") (pin "41") (pinfunction "P0.29_41") (pintype "bidirectional"))
    )
    (net (code "82") (name "P0.30") (class "Default")
      (node (ref "U2") (pin "42") (pinfunction "P0.30_42") (pintype "bidirectional"))
    )
    (net (code "83") (name "P0.31") (class "Default")
      (node (ref "U2") (pin "43") (pinfunction "P0.31_43") (pintype "bidirectional"))
    )
    (net (code "84") (name "POL") (class "Default")
      (node (ref "Q1") (pin "3") (pinfunction "D_3") (pintype "bidirectional"))
      (node (ref "R1") (pin "1") (pinfunction "1_1") (pintype "passive"))
      (node (ref "U$2") (pin "27") (pinfunction "POL_27") (pintype "bidirectional"))
    )
    (net (code "85") (name "RF") (class "Default")
      (node (ref "C5") (pin "1") (pinfunction "1_1") (pintype "passive"))
      (node (ref "L2") (pin "2") (pinfunction "2_2") (pintype "passive"))
    )
    (net (code "86") (name "SWDCLK") (class "Default")
      (node (ref "U2") (pin "25") (pinfunction "SWDCLK_25") (pintype "input"))
    )
    (net (code "87") (name "SWDIO") (class "Default")
      (node (ref "U2") (pin "26") (pinfunction "SWDIO_26") (pintype "bidirectional"))
    )
    (net (code "88") (name "VCC") (class "Default")
      (node (ref "C10") (pin "+") (pinfunction "+_+") (pintype "passive"))
      (node (ref "C4") (pin "1") (pinfunction "1_1") (pintype "passive"))
      (node (ref "U$3") (pin "1") (pinfunction "IN_1") (pintype "input"))
      (node (ref "U$4") (pin "8") (pinfunction "VIN_8") (pintype "bidirectional"))
      (node (ref "U$5") (pin "P$1") (pinfunction "1_P$1") (pintype "passive"))
    )
    (net (code "89") (name "unconnected-(U$1-CBS-Pad10)") (class "Default")
      (node (ref "U$1") (pin "10") (pinfunction "CBS_10") (pintype "bidirectional"))
    )
    (net (code "90") (name "unconnected-(U$1-SCK-Pad12)") (class "Default")
      (node (ref "U$1") (pin "12") (pinfunction "SCK_12") (pintype "bidirectional"))
    )
    (net (code "91") (name "unconnected-(U$1-SDO-Pad1)") (class "Default")
      (node (ref "U$1") (pin "1") (pinfunction "SDO_1") (pintype "bidirectional"))
    )
    (net (code "92") (name "unconnected-(U$1-SDX-Pad2)") (class "Default")
      (node (ref "U$1") (pin "2") (pinfunction "SDX_2") (pintype "bidirectional"))
    )
    (net (code "93") (name "unconnected-(U$2-DATAOUT-Pad23)") (class "Default")
      (node (ref "U$2") (pin "23") (pinfunction "DATAOUT_23") (pintype "bidirectional"))
    )
    (net (code "94") (name "unconnected-(U$2-HV-OUT25-Pad15)") (class "Default")
      (node (ref "U$2") (pin "15") (pinfunction "HV-OUT25_15") (pintype "bidirectional"))
    )
    (net (code "95") (name "unconnected-(U$2-HV-OUT26-Pad16)") (class "Default")
      (node (ref "U$2") (pin "16") (pinfunction "HV-OUT26_16") (pintype "bidirectional"))
    )
    (net (code "96") (name "unconnected-(U$2-HV-OUT27-Pad17)") (class "Default")
      (node (ref "U$2") (pin "17") (pinfunction "HV-OUT27_17") (pintype "bidirectional"))
    )
    (net (code "97") (name "unconnected-(U$2-HV-OUT28-Pad18)") (class "Default")
      (node (ref "U$2") (pin "18") (pinfunction "HV-OUT28_18") (pintype "bidirectional"))
    )
    (net (code "98") (name "unconnected-(U$2-HV-OUT29-Pad19)") (class "Default")
      (node (ref "U$2") (pin "19") (pinfunction "HV-OUT29_19") (pintype "bidirectional"))
    )
    (net (code "99") (name "unconnected-(U$2-HV-OUT30-Pad20)") (class "Default")
      (node (ref "U$2") (pin "20") (pinfunction "HV-OUT30_20") (pintype "bidirectional"))
    )
    (net (code "100") (name "unconnected-(U$2-HV-OUT31-Pad21)") (class "Default")
      (node (ref "U$2") (pin "21") (pinfunction "HV-OUT31_21") (pintype "bidirectional"))
    )
    (net (code "101") (name "unconnected-(U$2-HV-OUT32-Pad22)") (class "Default")
      (node (ref "U$2") (pin "22") (pinfunction "HV-OUT32_22") (pintype "bidirectional"))
    )
    (net (code "102") (name "unconnected-(U2-DCC-Pad47)") (class "Default")
      (node (ref "U2") (pin "47") (pinfunction "DCC_47") (pintype "output"))
    )
    (net (code "103") (name "unconnected-(U2-N.C.-Pad44)") (class "Default")
      (node (ref "U2") (pin "44") (pinfunction "N.C._44") (pintype "no_connect"))
    )
  )
)
